# Serial_Controlled_Motor_Driver.net
KiCad netlist of a schematic drawn in EAGLE
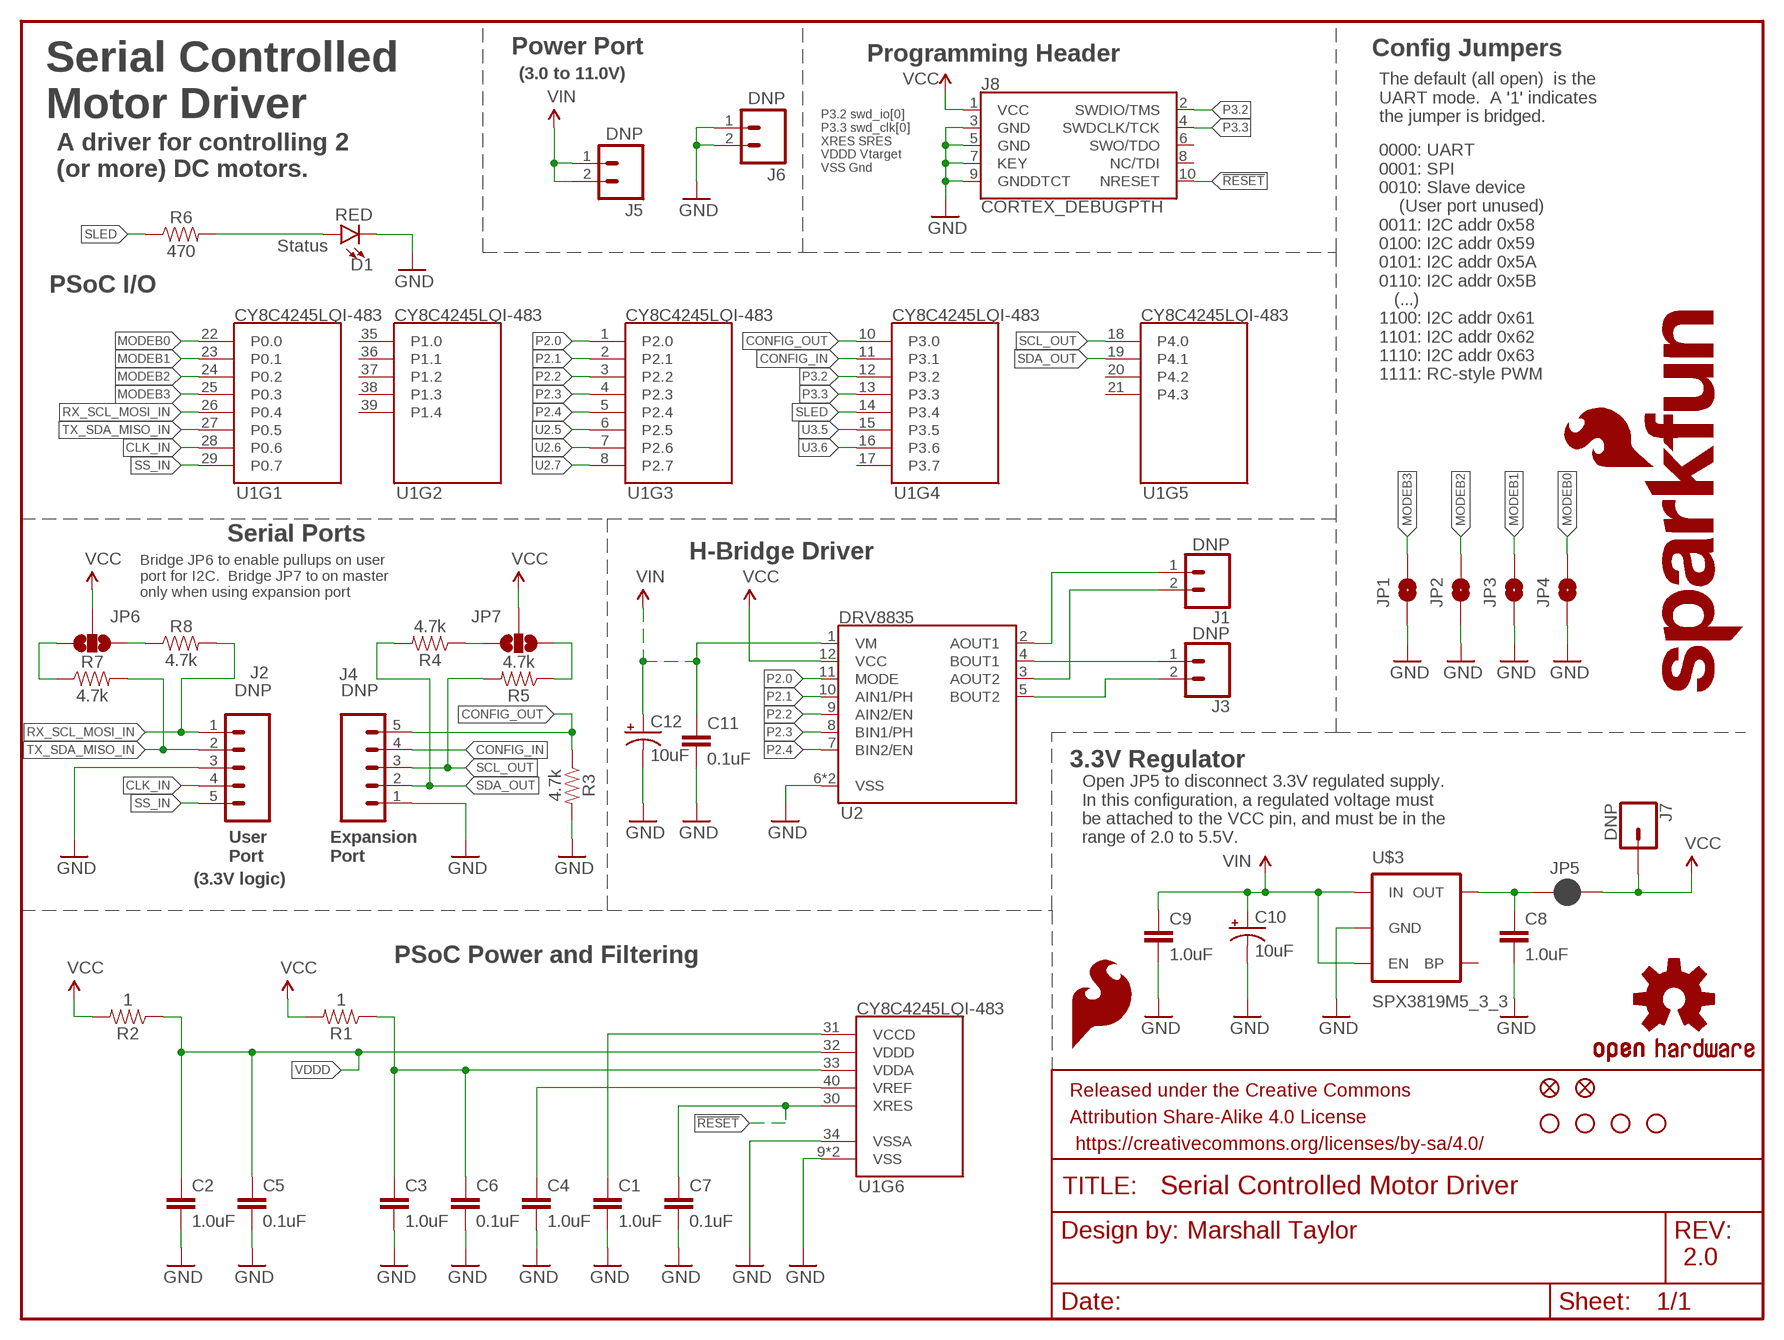
[diagram p0: schematic, sheet 1]

(export (version "E")
  (design (tool "Eeschema 10.0.6"))
  (components
    (comp (ref "C1")
      (value "1.0uF")
      (footprint "eagle-import:0402")
      (libsource (lib "eagle-import") (part "1.0UF-0402-16V-10%"))
    )
    (comp (ref "C2")
      (value "1.0uF")
      (footprint "eagle-import:0402")
      (libsource (lib "eagle-import") (part "1.0UF-0402-16V-10%"))
    )
    (comp (ref "C3")
      (value "1.0uF")
      (footprint "eagle-import:0402")
      (libsource (lib "eagle-import") (part "1.0UF-0402-16V-10%"))
    )
    (comp (ref "C4")
      (value "1.0uF")
      (footprint "eagle-import:0402")
      (libsource (lib "eagle-import") (part "1.0UF-0402-16V-10%"))
    )
    (comp (ref "C5")
      (value "0.1uF")
      (footprint "eagle-import:0402")
      (libsource (lib "eagle-import") (part "0.1UF-0402-16V-10%"))
    )
    (comp (ref "C6")
      (value "0.1uF")
      (footprint "eagle-import:0402")
      (libsource (lib "eagle-import") (part "0.1UF-0402-16V-10%"))
    )
    (comp (ref "C7")
      (value "0.1uF")
      (footprint "eagle-import:0402")
      (libsource (lib "eagle-import") (part "0.1UF-0402-16V-10%"))
    )
    (comp (ref "C8")
      (value "1.0uF")
      (footprint "eagle-import:0402")
      (libsource (lib "eagle-import") (part "1.0UF-0402-16V-10%"))
    )
    (comp (ref "C9")
      (value "1.0uF")
      (footprint "eagle-import:0402")
      (libsource (lib "eagle-import") (part "1.0UF-0402-16V-10%"))
    )
    (comp (ref "C10")
      (value "10uF")
      (footprint "eagle-import:EIA3216")
      (libsource (lib "eagle-import") (part "10UF-POLAR-EIA3216-16V-10%(TANT)"))
    )
    (comp (ref "C11")
      (value "0.1uF")
      (footprint "eagle-import:0402")
      (libsource (lib "eagle-import") (part "0.1UF-0402-16V-10%"))
    )
    (comp (ref "C12")
      (value "10uF")
      (footprint "eagle-import:EIA3216")
      (libsource (lib "eagle-import") (part "10UF-POLAR-EIA3216-16V-10%(TANT)"))
    )
    (comp (ref "D1")
      (value "RED")
      (footprint "eagle-import:LED-0603")
      (libsource (lib "eagle-import") (part "LED-RED0603"))
    )
    (comp (ref "FD1")
      (value "FIDUCIALUFIDUCIAL")
      (footprint "eagle-import:MICRO-FIDUCIAL")
      (libsource (lib "eagle-import") (part "FIDUCIALUFIDUCIAL"))
    )
    (comp (ref "FD2")
      (value "FIDUCIALUFIDUCIAL")
      (footprint "eagle-import:MICRO-FIDUCIAL")
      (libsource (lib "eagle-import") (part "FIDUCIALUFIDUCIAL"))
    )
    (comp (ref "FRAME1")
      (value "FRAME-LETTER")
      (footprint "eagle-import:CREATIVE_COMMONS")
      (libsource (lib "eagle-import") (part "FRAME-LETTER"))
    )
    (comp (ref "H1")
      (value "STAND-OFF")
      (footprint "eagle-import:STAND-OFF")
      (libsource (lib "eagle-import") (part "STAND-OFF"))
    )
    (comp (ref "H2")
      (value "STAND-OFF")
      (footprint "eagle-import:STAND-OFF")
      (libsource (lib "eagle-import") (part "STAND-OFF"))
    )
    (comp (ref "H3")
      (value "STAND-OFF")
      (footprint "eagle-import:STAND-OFF")
      (libsource (lib "eagle-import") (part "STAND-OFF"))
    )
    (comp (ref "H4")
      (value "STAND-OFF")
      (footprint "eagle-import:STAND-OFF")
      (libsource (lib "eagle-import") (part "STAND-OFF"))
    )
    (comp (ref "J1")
      (value "DNP")
      (footprint "eagle-import:1X02_NO_SILK")
      (libsource (lib "eagle-import") (part "CONN_021X02_NO_SILK"))
    )
    (comp (ref "J2")
      (value "DNP")
      (footprint "eagle-import:1X05")
      (libsource (lib "eagle-import") (part "M05PTH"))
    )
    (comp (ref "J3")
      (value "DNP")
      (footprint "eagle-import:1X02_NO_SILK")
      (libsource (lib "eagle-import") (part "CONN_021X02_NO_SILK"))
    )
    (comp (ref "J4")
      (value "DNP")
      (footprint "eagle-import:1X05")
      (libsource (lib "eagle-import") (part "M05PTH"))
    )
    (comp (ref "J5")
      (value "DNP")
      (footprint "eagle-import:1X02@1")
      (libsource (lib "eagle-import") (part "M02PTH"))
    )
    (comp (ref "J6")
      (value "DNP")
      (footprint "eagle-import:1X02@1")
      (libsource (lib "eagle-import") (part "M02PTH"))
    )
    (comp (ref "J7")
      (value "DNP")
      (footprint "eagle-import:1X01")
      (libsource (lib "eagle-import") (part "CONN_01PTH"))
    )
    (comp (ref "J8")
      (value "CORTEX_DEBUGPTH")
      (footprint "eagle-import:2X5-PTH-1.27MM")
      (libsource (lib "eagle-import") (part "CORTEX_DEBUGPTH"))
    )
    (comp (ref "JP1")
      (value "JUMPER-PAD-2")
      (footprint "eagle-import:PAD-JUMPER-2-NO_YES_SILK")
      (libsource (lib "eagle-import") (part "JUMPER-PAD-2-NOYES_SILK"))
    )
    (comp (ref "JP2")
      (value "JUMPER-PAD-2")
      (footprint "eagle-import:PAD-JUMPER-2-NO_YES_SILK")
      (libsource (lib "eagle-import") (part "JUMPER-PAD-2-NOYES_SILK"))
    )
    (comp (ref "JP3")
      (value "JUMPER-PAD-2")
      (footprint "eagle-import:PAD-JUMPER-2-NO_YES_SILK")
      (libsource (lib "eagle-import") (part "JUMPER-PAD-2-NOYES_SILK"))
    )
    (comp (ref "JP4")
      (value "JUMPER-PAD-2")
      (footprint "eagle-import:PAD-JUMPER-2-NO_YES_SILK")
      (libsource (lib "eagle-import") (part "JUMPER-PAD-2-NOYES_SILK"))
    )
    (comp (ref "JP5")
      (value "JUMPER-PAD-2")
      (footprint "eagle-import:PAD-JUMPER-2-NC_BY_PASTE_YES_SILK")
      (libsource (lib "eagle-import") (part "JUMPER-PAD-2-NC_BY_PASTE"))
    )
    (comp (ref "JP6")
      (value "JUMPER-PAD-3-NOYES_SILK")
      (footprint "eagle-import:PAD-JUMPER-3-NO_YES_SILK")
      (libsource (lib "eagle-import") (part "JUMPER-PAD-3-NOYES_SILK"))
    )
    (comp (ref "JP7")
      (value "JUMPER-PAD-3-NOYES_SILK")
      (footprint "eagle-import:PAD-JUMPER-3-NO_YES_SILK")
      (libsource (lib "eagle-import") (part "JUMPER-PAD-3-NOYES_SILK"))
    )
    (comp (ref "LOGO1")
      (value "SFE_LOGO_FLAME.1_INCH")
      (footprint "eagle-import:SFE_LOGO_FLAME_.1")
      (libsource (lib "eagle-import") (part "SFE_LOGO_FLAME.1_INCH"))
    )
    (comp (ref "LOGO2")
      (value "OSHW-LOGOMINI")
      (footprint "eagle-import:OSHW-LOGO-MINI")
      (libsource (lib "eagle-import") (part "OSHW-LOGOMINI"))
    )
    (comp (ref "LOGO3")
      (value "SFE_LOGO_NAME_FLAME.1_INCH")
      (footprint "eagle-import:SFE_LOGO_NAME_FLAME_.1")
      (libsource (lib "eagle-import") (part "SFE_LOGO_NAME_FLAME.1_INCH"))
    )
    (comp (ref "R1")
      (value "1")
      (footprint "eagle-import:0603")
      (libsource (lib "eagle-import") (part "1OHM-0603-1/10W-1%"))
    )
    (comp (ref "R2")
      (value "1")
      (footprint "eagle-import:0603")
      (libsource (lib "eagle-import") (part "1OHM-0603-1/10W-1%"))
    )
    (comp (ref "R3")
      (value "4.7k")
      (footprint "eagle-import:0603")
      (libsource (lib "eagle-import") (part "4.7KOHM-0603-1/10W-1%"))
    )
    (comp (ref "R4")
      (value "4.7k")
      (footprint "eagle-import:0603")
      (libsource (lib "eagle-import") (part "4.7KOHM-0603-1/10W-1%"))
    )
    (comp (ref "R5")
      (value "4.7k")
      (footprint "eagle-import:0603")
      (libsource (lib "eagle-import") (part "4.7KOHM-0603-1/10W-1%"))
    )
    (comp (ref "R6")
      (value "470")
      (footprint "eagle-import:0603")
      (libsource (lib "eagle-import") (part "470OHM-0603-1/10W-1%"))
    )
    (comp (ref "R7")
      (value "4.7k")
      (footprint "eagle-import:0603")
      (libsource (lib "eagle-import") (part "4.7KOHM-0603-1/10W-1%"))
    )
    (comp (ref "R8")
      (value "4.7k")
      (footprint "eagle-import:0603")
      (libsource (lib "eagle-import") (part "4.7KOHM-0603-1/10W-1%"))
    )
    (comp (ref "U$3")
      (value "SPX3819M5_3_3")
      (footprint "eagle-import:SOT-23-5-VREG")
      (libsource (lib "eagle-import") (part "SPX3819"))
    )
    (comp (ref "U1")
      (value "CY8C4245LQI-483")
      (footprint "eagle-import:QFN-40")
      (libsource (lib "eagle-import") (part "CY8C4245LQI"))
    )
    (comp (ref "U2")
      (value "DRV8835")
      (footprint "eagle-import:WSON-12")
      (fields (field (name "PROD_ID") "IC-13342"))
      (libsource (lib "eagle-import") (part "DRV883X"))
    )
  )
  (nets
    (net (code "1") (name "/~{RESET}") (class "Default")
      (node (ref "C7") (pin "1") (pinfunction "1_1") (pintype "passive"))
      (node (ref "J8") (pin "10") (pinfunction "NRESET_10") (pintype "bidirectional"))
      (node (ref "U1") (pin "30") (pinfunction "XRES_30") (pintype "bidirectional"))
    )
    (net (code "2") (name "CLK_IN") (class "Default")
      (node (ref "J2") (pin "4") (pinfunction "4_4") (pintype "passive"))
      (node (ref "U1") (pin "28") (pinfunction "P0.6_28") (pintype "bidirectional"))
    )
    (net (code "3") (name "CONFIG_IN") (class "Default")
      (node (ref "J4") (pin "4") (pinfunction "4_4") (pintype "passive"))
      (node (ref "U1") (pin "11") (pinfunction "P3.1_11") (pintype "bidirectional"))
    )
    (net (code "4") (name "CONFIG_OUT") (class "Default")
      (node (ref "J4") (pin "5") (pinfunction "5_5") (pintype "passive"))
      (node (ref "R3") (pin "1") (pinfunction "1_1") (pintype "passive"))
      (node (ref "U1") (pin "10") (pinfunction "P3.0_10") (pintype "bidirectional"))
    )
    (net (code "5") (name "GND") (class "Default")
      (node (ref "C1") (pin "2") (pinfunction "2_2") (pintype "passive"))
      (node (ref "C10") (pin "-") (pinfunction "-_-") (pintype "passive"))
      (node (ref "C11") (pin "2") (pinfunction "2_2") (pintype "passive"))
      (node (ref "C12") (pin "-") (pinfunction "-_-") (pintype "passive"))
      (node (ref "C2") (pin "2") (pinfunction "2_2") (pintype "passive"))
      (node (ref "C3") (pin "2") (pinfunction "2_2") (pintype "passive"))
      (node (ref "C4") (pin "2") (pinfunction "2_2") (pintype "passive"))
      (node (ref "C5") (pin "2") (pinfunction "2_2") (pintype "passive"))
      (node (ref "C6") (pin "2") (pinfunction "2_2") (pintype "passive"))
      (node (ref "C7") (pin "2") (pinfunction "2_2") (pintype "passive"))
      (node (ref "C8") (pin "2") (pinfunction "2_2") (pintype "passive"))
      (node (ref "C9") (pin "2") (pinfunction "2_2") (pintype "passive"))
      (node (ref "D1") (pin "C") (pinfunction "C_C") (pintype "passive"))
      (node (ref "J2") (pin "3") (pinfunction "3_3") (pintype "passive"))
      (node (ref "J4") (pin "1") (pinfunction "1_1") (pintype "passive"))
      (node (ref "J6") (pin "1") (pinfunction "1_1") (pintype "passive"))
      (node (ref "J6") (pin "2") (pinfunction "2_2") (pintype "passive"))
      (node (ref "J8") (pin "3") (pinfunction "GND_3") (pintype "bidirectional"))
      (node (ref "J8") (pin "5") (pinfunction "GND_5") (pintype "bidirectional"))
      (node (ref "J8") (pin "7") (pinfunction "KEY_7") (pintype "bidirectional"))
      (node (ref "J8") (pin "9") (pinfunction "GNDDTCT_9") (pintype "bidirectional"))
      (node (ref "JP1") (pin "1") (pinfunction "1_1") (pintype "passive"))
      (node (ref "JP2") (pin "1") (pinfunction "1_1") (pintype "passive"))
      (node (ref "JP3") (pin "1") (pinfunction "1_1") (pintype "passive"))
      (node (ref "JP4") (pin "1") (pinfunction "1_1") (pintype "passive"))
      (node (ref "R3") (pin "2") (pinfunction "2_2") (pintype "passive"))
      (node (ref "U$3") (pin "2") (pinfunction "GND_2") (pintype "input"))
      (node (ref "U1") (pin "34") (pinfunction "VSSA_34") (pintype "bidirectional"))
      (node (ref "U1") (pin "9") (pinfunction "VSS_9") (pintype "bidirectional"))
      (node (ref "U1") (pin "EP") (pinfunction "VSS_EP") (pintype "bidirectional"))
      (node (ref "U2") (pin "6") (pinfunction "VSS_6") (pintype "bidirectional"))
      (node (ref "U2") (pin "PAD") (pinfunction "VSS_PAD") (pintype "bidirectional"))
    )
    (net (code "6") (name "MODEB0") (class "Default")
      (node (ref "JP4") (pin "2") (pinfunction "2_2") (pintype "passive"))
      (node (ref "U1") (pin "22") (pinfunction "P0.0_22") (pintype "bidirectional"))
    )
    (net (code "7") (name "MODEB1") (class "Default")
      (node (ref "JP3") (pin "2") (pinfunction "2_2") (pintype "passive"))
      (node (ref "U1") (pin "23") (pinfunction "P0.1_23") (pintype "bidirectional"))
    )
    (net (code "8") (name "MODEB2") (class "Default")
      (node (ref "JP2") (pin "2") (pinfunction "2_2") (pintype "passive"))
      (node (ref "U1") (pin "24") (pinfunction "P0.2_24") (pintype "bidirectional"))
    )
    (net (code "9") (name "MODEB3") (class "Default")
      (node (ref "JP1") (pin "2") (pinfunction "2_2") (pintype "passive"))
      (node (ref "U1") (pin "25") (pinfunction "P0.3_25") (pintype "bidirectional"))
    )
    (net (code "10") (name "Net-(D1-PadA)") (class "Default")
      (node (ref "D1") (pin "A") (pinfunction "A_A") (pintype "passive"))
      (node (ref "R6") (pin "2") (pinfunction "2_2") (pintype "passive"))
    )
    (net (code "11") (name "Net-(JP6-Pad1)") (class "Default")
      (node (ref "JP6") (pin "1") (pinfunction "1_1") (pintype "passive"))
      (node (ref "R8") (pin "1") (pinfunction "1_1") (pintype "passive"))
    )
    (net (code "12") (name "Net-(JP6-Pad3)") (class "Default")
      (node (ref "JP6") (pin "3") (pinfunction "3_3") (pintype "passive"))
      (node (ref "R7") (pin "1") (pinfunction "1_1") (pintype "passive"))
    )
    (net (code "13") (name "Net-(JP7-Pad1)") (class "Default")
      (node (ref "JP7") (pin "1") (pinfunction "1_1") (pintype "passive"))
      (node (ref "R4") (pin "1") (pinfunction "1_1") (pintype "passive"))
    )
    (net (code "14") (name "Net-(JP7-Pad3)") (class "Default")
      (node (ref "JP7") (pin "3") (pinfunction "3_3") (pintype "passive"))
      (node (ref "R5") (pin "1") (pinfunction "1_1") (pintype "passive"))
    )
    (net (code "15") (name "Net-(U$3-OUT)") (class "Default")
      (node (ref "C8") (pin "1") (pinfunction "1_1") (pintype "passive"))
      (node (ref "JP5") (pin "1") (pinfunction "1_1") (pintype "passive"))
      (node (ref "U$3") (pin "5") (pinfunction "OUT_5") (pintype "passive"))
    )
    (net (code "16") (name "Net-(U1F-VCCD)") (class "Default")
      (node (ref "C1") (pin "1") (pinfunction "1_1") (pintype "passive"))
      (node (ref "U1") (pin "31") (pinfunction "VCCD_31") (pintype "bidirectional"))
    )
    (net (code "17") (name "Net-(U1F-VDDA)") (class "Default")
      (node (ref "C3") (pin "1") (pinfunction "1_1") (pintype "passive"))
      (node (ref "C6") (pin "1") (pinfunction "1_1") (pintype "passive"))
      (node (ref "R1") (pin "1") (pinfunction "1_1") (pintype "passive"))
      (node (ref "U1") (pin "33") (pinfunction "VDDA_33") (pintype "bidirectional"))
    )
    (net (code "18") (name "Net-(U1F-VREF)") (class "Default")
      (node (ref "C4") (pin "1") (pinfunction "1_1") (pintype "passive"))
      (node (ref "U1") (pin "40") (pinfunction "VREF_40") (pintype "bidirectional"))
    )
    (net (code "19") (name "Net-(U2-AOUT1)") (class "Default")
      (node (ref "J1") (pin "1") (pinfunction "1_1") (pintype "passive"))
      (node (ref "U2") (pin "2") (pinfunction "AOUT1_2") (pintype "bidirectional"))
    )
    (net (code "20") (name "Net-(U2-AOUT2)") (class "Default")
      (node (ref "J1") (pin "2") (pinfunction "2_2") (pintype "passive"))
      (node (ref "U2") (pin "3") (pinfunction "AOUT2_3") (pintype "bidirectional"))
    )
    (net (code "21") (name "Net-(U2-BOUT1)") (class "Default")
      (node (ref "J3") (pin "1") (pinfunction "1_1") (pintype "passive"))
      (node (ref "U2") (pin "4") (pinfunction "BOUT1_4") (pintype "bidirectional"))
    )
    (net (code "22") (name "Net-(U2-BOUT2)") (class "Default")
      (node (ref "J3") (pin "2") (pinfunction "2_2") (pintype "passive"))
      (node (ref "U2") (pin "5") (pinfunction "BOUT2_5") (pintype "bidirectional"))
    )
    (net (code "23") (name "P2.0") (class "Default")
      (node (ref "U1") (pin "1") (pinfunction "P2.0_1") (pintype "bidirectional"))
      (node (ref "U2") (pin "11") (pinfunction "MODE_11") (pintype "bidirectional"))
    )
    (net (code "24") (name "P2.1") (class "Default")
      (node (ref "U1") (pin "2") (pinfunction "P2.1_2") (pintype "bidirectional"))
      (node (ref "U2") (pin "10") (pinfunction "AIN1/PH_10") (pintype "bidirectional"))
    )
    (net (code "25") (name "P2.2") (class "Default")
      (node (ref "U1") (pin "3") (pinfunction "P2.2_3") (pintype "bidirectional"))
      (node (ref "U2") (pin "9") (pinfunction "AIN2/EN_9") (pintype "bidirectional"))
    )
    (net (code "26") (name "P2.3") (class "Default")
      (node (ref "U1") (pin "4") (pinfunction "P2.3_4") (pintype "bidirectional"))
      (node (ref "U2") (pin "8") (pinfunction "BIN1/PH_8") (pintype "bidirectional"))
    )
    (net (code "27") (name "P2.4") (class "Default")
      (node (ref "U1") (pin "5") (pinfunction "P2.4_5") (pintype "bidirectional"))
      (node (ref "U2") (pin "7") (pinfunction "BIN2/EN_7") (pintype "bidirectional"))
    )
    (net (code "28") (name "P3.2") (class "Default")
      (node (ref "J8") (pin "2") (pinfunction "SWDIO/TMS_2") (pintype "bidirectional"))
      (node (ref "U1") (pin "12") (pinfunction "P3.2_12") (pintype "bidirectional"))
    )
    (net (code "29") (name "P3.3") (class "Default")
      (node (ref "J8") (pin "4") (pinfunction "SWDCLK/TCK_4") (pintype "bidirectional"))
      (node (ref "U1") (pin "13") (pinfunction "P3.3_13") (pintype "bidirectional"))
    )
    (net (code "30") (name "RX_SCL_MOSI_IN") (class "Default")
      (node (ref "J2") (pin "1") (pinfunction "1_1") (pintype "passive"))
      (node (ref "R8") (pin "2") (pinfunction "2_2") (pintype "passive"))
      (node (ref "U1") (pin "26") (pinfunction "P0.4_26") (pintype "bidirectional"))
    )
    (net (code "31") (name "SCL_OUT") (class "Default")
      (node (ref "J4") (pin "3") (pinfunction "3_3") (pintype "passive"))
      (node (ref "R5") (pin "2") (pinfunction "2_2") (pintype "passive"))
      (node (ref "U1") (pin "18") (pinfunction "P4.0_18") (pintype "bidirectional"))
    )
    (net (code "32") (name "SDA_OUT") (class "Default")
      (node (ref "J4") (pin "2") (pinfunction "2_2") (pintype "passive"))
      (node (ref "R4") (pin "2") (pinfunction "2_2") (pintype "passive"))
      (node (ref "U1") (pin "19") (pinfunction "P4.1_19") (pintype "bidirectional"))
    )
    (net (code "33") (name "SLED") (class "Default")
      (node (ref "R6") (pin "1") (pinfunction "1_1") (pintype "passive"))
      (node (ref "U1") (pin "14") (pinfunction "P3.4_14") (pintype "bidirectional"))
    )
    (net (code "34") (name "SS_IN") (class "Default")
      (node (ref "J2") (pin "5") (pinfunction "5_5") (pintype "passive"))
      (node (ref "U1") (pin "29") (pinfunction "P0.7_29") (pintype "bidirectional"))
    )
    (net (code "35") (name "TX_SDA_MISO_IN") (class "Default")
      (node (ref "J2") (pin "2") (pinfunction "2_2") (pintype "passive"))
      (node (ref "R7") (pin "2") (pinfunction "2_2") (pintype "passive"))
      (node (ref "U1") (pin "27") (pinfunction "P0.5_27") (pintype "bidirectional"))
    )
    (net (code "36") (name "U2.5") (class "Default")
      (node (ref "U1") (pin "6") (pinfunction "P2.5_6") (pintype "bidirectional"))
    )
    (net (code "37") (name "U2.6") (class "Default")
      (node (ref "U1") (pin "7") (pinfunction "P2.6_7") (pintype "bidirectional"))
    )
    (net (code "38") (name "U2.7") (class "Default")
      (node (ref "U1") (pin "8") (pinfunction "P2.7_8") (pintype "bidirectional"))
    )
    (net (code "39") (name "U3.5") (class "Default")
      (node (ref "U1") (pin "15") (pinfunction "P3.5_15") (pintype "bidirectional"))
    )
    (net (code "40") (name "U3.6") (class "Default")
      (node (ref "U1") (pin "16") (pinfunction "P3.6_16") (pintype "bidirectional"))
    )
    (net (code "41") (name "VCC") (class "Default")
      (node (ref "J7") (pin "1") (pinfunction "1_1") (pintype "passive"))
      (node (ref "J8") (pin "1") (pinfunction "VCC_1") (pintype "bidirectional"))
      (node (ref "JP5") (pin "2") (pinfunction "2_2") (pintype "passive"))
      (node (ref "JP6") (pin "2") (pinfunction "2_2") (pintype "passive"))
      (node (ref "JP7") (pin "2") (pinfunction "2_2") (pintype "passive"))
      (node (ref "R1") (pin "2") (pinfunction "2_2") (pintype "passive"))
      (node (ref "R2") (pin "2") (pinfunction "2_2") (pintype "passive"))
      (node (ref "U2") (pin "12") (pinfunction "VCC_12") (pintype "bidirectional"))
    )
    (net (code "42") (name "VDDD") (class "Default")
      (node (ref "C2") (pin "1") (pinfunction "1_1") (pintype "passive"))
      (node (ref "C5") (pin "1") (pinfunction "1_1") (pintype "passive"))
      (node (ref "R2") (pin "1") (pinfunction "1_1") (pintype "passive"))
      (node (ref "U1") (pin "32") (pinfunction "VDDD_32") (pintype "bidirectional"))
    )
    (net (code "43") (name "VIN") (class "Default")
      (node (ref "C10") (pin "+") (pinfunction "+_+") (pintype "passive"))
      (node (ref "C11") (pin "1") (pinfunction "1_1") (pintype "passive"))
      (node (ref "C12") (pin "+") (pinfunction "+_+") (pintype "passive"))
      (node (ref "C9") (pin "1") (pinfunction "1_1") (pintype "passive"))
      (node (ref "J5") (pin "1") (pinfunction "1_1") (pintype "passive"))
      (node (ref "J5") (pin "2") (pinfunction "2_2") (pintype "passive"))
      (node (ref "U$3") (pin "1") (pinfunction "IN_1") (pintype "input"))
      (node (ref "U$3") (pin "3") (pinfunction "EN_3") (pintype "input"))
      (node (ref "U2") (pin "1") (pinfunction "VM_1") (pintype "bidirectional"))
    )
    (net (code "44") (name "unconnected-(J8-NC{slash}TDI-Pad8)") (class "Default")
      (node (ref "J8") (pin "8") (pinfunction "NC/TDI_8") (pintype "bidirectional"))
    )
    (net (code "45") (name "unconnected-(J8-SWO{slash}TDO-Pad6)") (class "Default")
      (node (ref "J8") (pin "6") (pinfunction "SWO/TDO_6") (pintype "bidirectional"))
    )
    (net (code "46") (name "unconnected-(U$3-BP-Pad4)") (class "Default")
      (node (ref "U$3") (pin "4") (pinfunction "BP_4") (pintype "input"))
    )
    (net (code "47") (name "unconnected-(U1B-P1.0-Pad35)") (class "Default")
      (node (ref "U1") (pin "35") (pinfunction "P1.0_35") (pintype "bidirectional"))
    )
    (net (code "48") (name "unconnected-(U1B-P1.1-Pad36)") (class "Default")
      (node (ref "U1") (pin "36") (pinfunction "P1.1_36") (pintype "bidirectional"))
    )
    (net (code "49") (name "unconnected-(U1B-P1.2-Pad37)") (class "Default")
      (node (ref "U1") (pin "37") (pinfunction "P1.2_37") (pintype "bidirectional"))
    )
    (net (code "50") (name "unconnected-(U1B-P1.3-Pad38)") (class "Default")
      (node (ref "U1") (pin "38") (pinfunction "P1.3_38") (pintype "bidirectional"))
    )
    (net (code "51") (name "unconnected-(U1B-P1.4-Pad39)") (class "Default")
      (node (ref "U1") (pin "39") (pinfunction "P1.4_39") (pintype "bidirectional"))
    )
    (net (code "52") (name "unconnected-(U1D-P3.7-Pad17)") (class "Default")
      (node (ref "U1") (pin "17") (pinfunction "P3.7_17") (pintype "bidirectional"))
    )
    (net (code "53") (name "unconnected-(U1E-P4.2-Pad20)") (class "Default")
      (node (ref "U1") (pin "20") (pinfunction "P4.2_20") (pintype "bidirectional"))
    )
    (net (code "54") (name "unconnected-(U1E-P4.3-Pad21)") (class "Default")
      (node (ref "U1") (pin "21") (pinfunction "P4.3_21") (pintype "bidirectional"))
    )
  )
)
